# PCB_Design.net
KiCad netlist of a schematic drawn in EAGLE
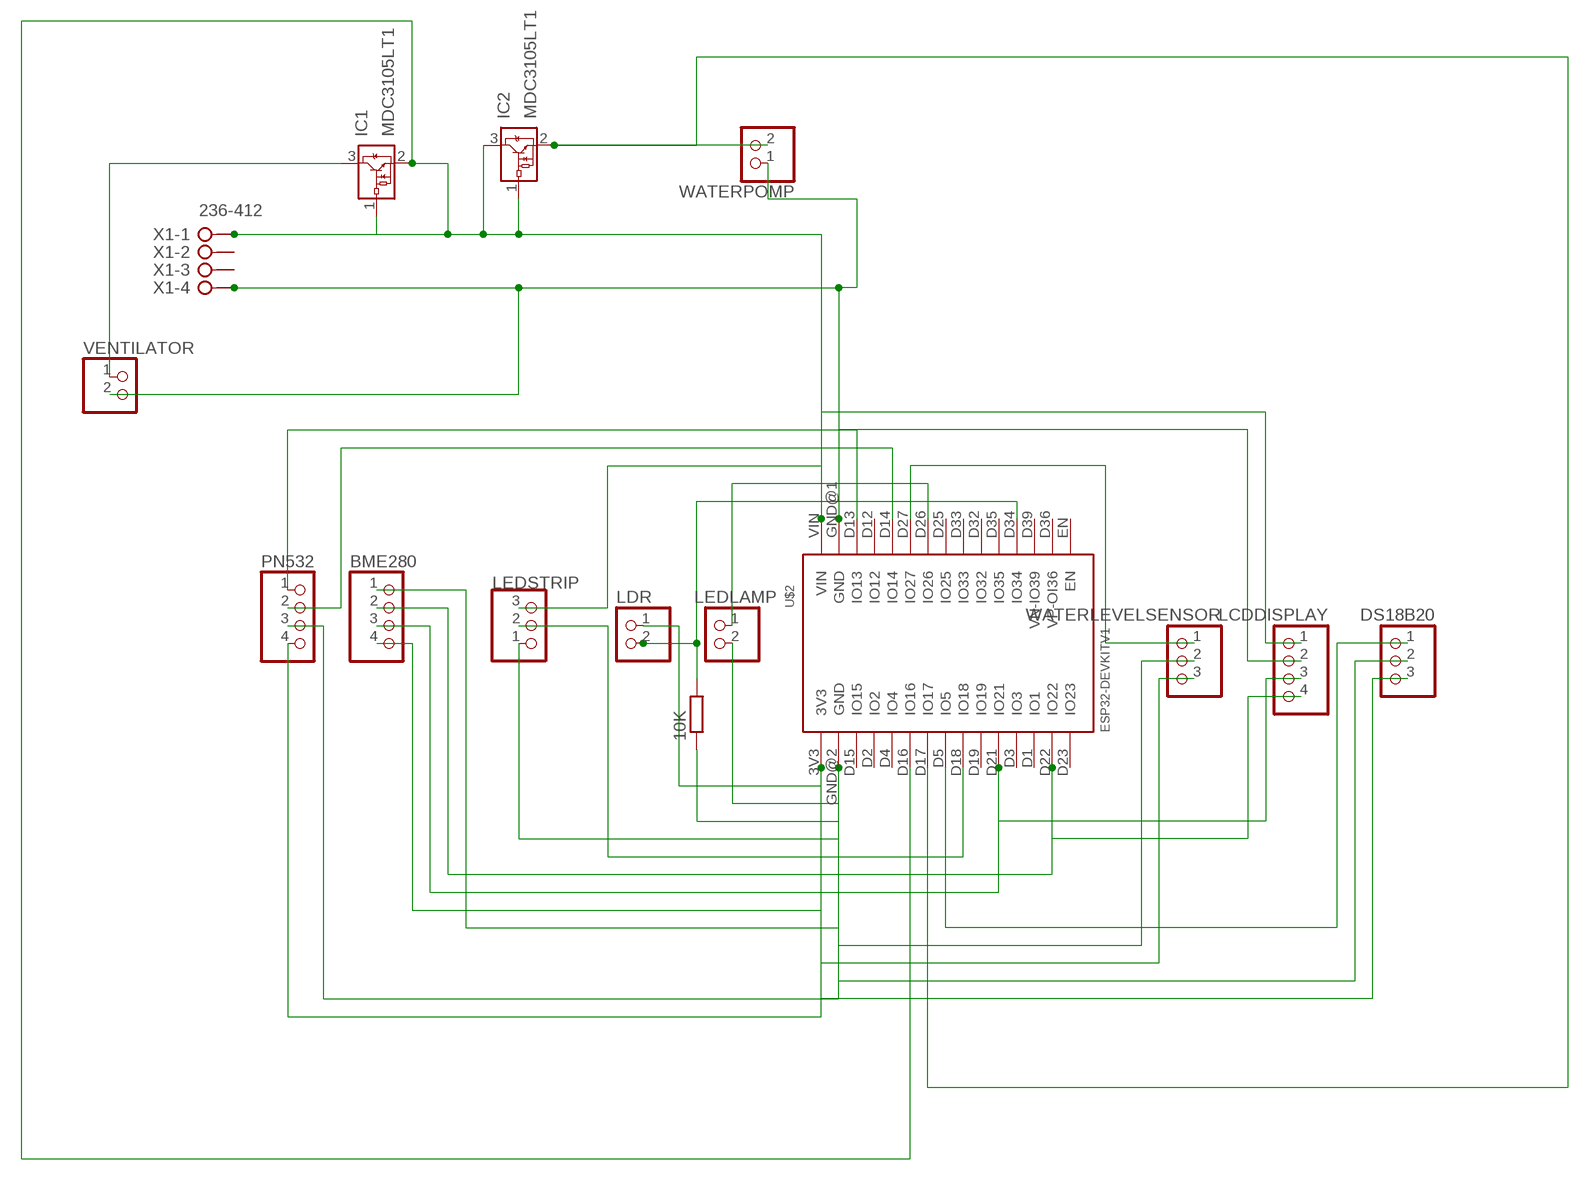
[diagram p0: schematic, sheet 1]

(export (version "E")
  (design (tool "Eeschema 10.0.6"))
  (components
    (comp (ref "10K")
      (value "R-EU_0204/7")
      (footprint "eagle-import:0204_7")
      (libsource (lib "eagle-import") (part "R-EU_0204/7"))
    )
    (comp (ref "BME280")
      (value "PINHD-1X4")
      (footprint "eagle-import:1X04")
      (libsource (lib "eagle-import") (part "PINHD-1X4"))
    )
    (comp (ref "DS18B20")
      (value "PINHD-1X3")
      (footprint "eagle-import:1X03")
      (libsource (lib "eagle-import") (part "PINHD-1X3"))
    )
    (comp (ref "IC1")
      (value "MDC3105LT1")
      (footprint "eagle-import:SOT23")
      (fields (field (name "MF") "ON SEMICONDUCTOR"))
      (libsource (lib "eagle-import") (part "MDC3105LT1"))
    )
    (comp (ref "IC2")
      (value "MDC3105LT1")
      (footprint "eagle-import:SOT23")
      (fields (field (name "MF") "ON SEMICONDUCTOR"))
      (libsource (lib "eagle-import") (part "MDC3105LT1"))
    )
    (comp (ref "LCDDISPLAY")
      (value "PINHD-1X4")
      (footprint "eagle-import:1X04")
      (libsource (lib "eagle-import") (part "PINHD-1X4"))
    )
    (comp (ref "LDR")
      (value "PINHD-1X2")
      (footprint "eagle-import:1X02")
      (libsource (lib "eagle-import") (part "PINHD-1X2"))
    )
    (comp (ref "LEDLAMP")
      (value "PINHD-1X2")
      (footprint "eagle-import:1X02")
      (libsource (lib "eagle-import") (part "PINHD-1X2"))
    )
    (comp (ref "LEDSTRIP")
      (value "PINHD-1X3")
      (footprint "eagle-import:1X03")
      (libsource (lib "eagle-import") (part "PINHD-1X3"))
    )
    (comp (ref "PN532")
      (value "PINHD-1X4")
      (footprint "eagle-import:1X04")
      (libsource (lib "eagle-import") (part "PINHD-1X4"))
    )
    (comp (ref "U$2")
      (value "ESP32DEVKITV1")
      (footprint "eagle-import:ESP32-DEVKITV1")
      (libsource (lib "eagle-import") (part "ESP32DEVKITV1"))
    )
    (comp (ref "VENTILATOR")
      (value "PINHD-1X2")
      (footprint "eagle-import:1X02")
      (libsource (lib "eagle-import") (part "PINHD-1X2"))
    )
    (comp (ref "WATERLEVELSENSOR")
      (value "PINHD-1X3")
      (footprint "eagle-import:1X03")
      (libsource (lib "eagle-import") (part "PINHD-1X3"))
    )
    (comp (ref "WATERPOMP")
      (value "PINHD-1X2")
      (footprint "eagle-import:1X02")
      (libsource (lib "eagle-import") (part "PINHD-1X2"))
    )
    (comp (ref "X1")
      (value "236-412")
      (footprint "eagle-import:236-412")
      (fields (field (name "MF") "Wago Corporation") (field (name "MPN") "0236-0412"))
      (libsource (lib "eagle-import") (part "236-412"))
    )
  )
  (nets
    (net (code "1") (name "Net-(10K-Pad1)") (class "Default")
      (node (ref "10K") (pin "1") (pinfunction "1_1") (pintype "passive"))
      (node (ref "BME280") (pin "1") (pinfunction "1_1") (pintype "passive"))
      (node (ref "DS18B20") (pin "2") (pinfunction "2_2") (pintype "passive"))
      (node (ref "LEDLAMP") (pin "2") (pinfunction "2_2") (pintype "passive"))
      (node (ref "LEDSTRIP") (pin "1") (pinfunction "1_1") (pintype "passive"))
      (node (ref "PN532") (pin "3") (pinfunction "3_3") (pintype "passive"))
      (node (ref "U$2") (pin "GND@2") (pinfunction "GND_GND@2") (pintype "bidirectional"))
      (node (ref "WATERLEVELSENSOR") (pin "2") (pinfunction "2_2") (pintype "passive"))
    )
    (net (code "2") (name "Net-(BME280-Pad4)") (class "Default")
      (node (ref "BME280") (pin "4") (pinfunction "4_4") (pintype "passive"))
      (node (ref "DS18B20") (pin "3") (pinfunction "3_3") (pintype "passive"))
      (node (ref "LDR") (pin "1") (pinfunction "1_1") (pintype "passive"))
      (node (ref "PN532") (pin "4") (pinfunction "4_4") (pintype "passive"))
      (node (ref "U$2") (pin "3V3") (pinfunction "3V3_3V3") (pintype "bidirectional"))
      (node (ref "WATERLEVELSENSOR") (pin "3") (pinfunction "3_3") (pintype "passive"))
    )
    (net (code "3") (name "Net-(IC1-GND)") (class "Default")
      (node (ref "IC1") (pin "1") (pinfunction "VIN_1") (pintype "passive"))
      (node (ref "IC1") (pin "2") (pinfunction "GND_2") (pintype "passive"))
      (node (ref "IC2") (pin "1") (pinfunction "VIN_1") (pintype "passive"))
      (node (ref "IC2") (pin "3") (pinfunction "VOUT_3") (pintype "passive"))
      (node (ref "LCDDISPLAY") (pin "1") (pinfunction "1_1") (pintype "passive"))
      (node (ref "LEDSTRIP") (pin "3") (pinfunction "3_3") (pintype "passive"))
      (node (ref "U$2") (pin "D16") (pinfunction "IO16_D16") (pintype "bidirectional"))
      (node (ref "U$2") (pin "VIN") (pinfunction "VIN_VIN") (pintype "bidirectional"))
      (node (ref "X1") (pin "1@1") (pinfunction "KL1_1@1") (pintype "passive"))
    )
    (net (code "4") (name "Net-(IC1-VOUT)") (class "Default")
      (node (ref "IC1") (pin "3") (pinfunction "VOUT_3") (pintype "passive"))
      (node (ref "VENTILATOR") (pin "1") (pinfunction "1_1") (pintype "passive"))
    )
    (net (code "5") (name "Net-(IC2-GND)") (class "Default")
      (node (ref "IC2") (pin "2") (pinfunction "GND_2") (pintype "passive"))
      (node (ref "U$2") (pin "D17") (pinfunction "IO17_D17") (pintype "bidirectional"))
      (node (ref "WATERPOMP") (pin "2") (pinfunction "2_2") (pintype "passive"))
    )
    (net (code "6") (name "Net-(U$2-IO5)") (class "Default")
      (node (ref "DS18B20") (pin "1") (pinfunction "1_1") (pintype "passive"))
      (node (ref "U$2") (pin "D5") (pinfunction "IO5_D5") (pintype "bidirectional"))
    )
    (net (code "7") (name "Net-(U$2-IO13)") (class "Default")
      (node (ref "PN532") (pin "1") (pinfunction "1_1") (pintype "passive"))
      (node (ref "U$2") (pin "D13") (pinfunction "IO13_D13") (pintype "bidirectional"))
    )
    (net (code "8") (name "Net-(U$2-IO14)") (class "Default")
      (node (ref "PN532") (pin "2") (pinfunction "2_2") (pintype "passive"))
      (node (ref "U$2") (pin "D14") (pinfunction "IO14_D14") (pintype "bidirectional"))
    )
    (net (code "9") (name "Net-(U$2-IO18)") (class "Default")
      (node (ref "LEDSTRIP") (pin "2") (pinfunction "2_2") (pintype "passive"))
      (node (ref "U$2") (pin "D18") (pinfunction "IO18_D18") (pintype "bidirectional"))
    )
    (net (code "10") (name "Net-(U$2-IO21)") (class "Default")
      (node (ref "BME280") (pin "3") (pinfunction "3_3") (pintype "passive"))
      (node (ref "LCDDISPLAY") (pin "3") (pinfunction "3_3") (pintype "passive"))
      (node (ref "U$2") (pin "D21") (pinfunction "IO21_D21") (pintype "bidirectional"))
    )
    (net (code "11") (name "Net-(U$2-IO22)") (class "Default")
      (node (ref "BME280") (pin "2") (pinfunction "2_2") (pintype "passive"))
      (node (ref "LCDDISPLAY") (pin "4") (pinfunction "4_4") (pintype "passive"))
      (node (ref "U$2") (pin "D22") (pinfunction "IO22_D22") (pintype "bidirectional"))
    )
    (net (code "12") (name "Net-(U$2-IO26)") (class "Default")
      (node (ref "LEDLAMP") (pin "1") (pinfunction "1_1") (pintype "passive"))
      (node (ref "U$2") (pin "D26") (pinfunction "IO26_D26") (pintype "bidirectional"))
    )
    (net (code "13") (name "Net-(U$2-IO27)") (class "Default")
      (node (ref "U$2") (pin "D27") (pinfunction "IO27_D27") (pintype "bidirectional"))
      (node (ref "WATERLEVELSENSOR") (pin "1") (pinfunction "1_1") (pintype "passive"))
    )
    (net (code "14") (name "Net-(U$2-IO34)") (class "Default")
      (node (ref "10K") (pin "2") (pinfunction "2_2") (pintype "passive"))
      (node (ref "LDR") (pin "2") (pinfunction "2_2") (pintype "passive"))
      (node (ref "U$2") (pin "D34") (pinfunction "IO34_D34") (pintype "bidirectional"))
    )
    (net (code "15") (name "Net-(X1G-KL1)") (class "Default")
      (node (ref "LCDDISPLAY") (pin "2") (pinfunction "2_2") (pintype "passive"))
      (node (ref "U$2") (pin "GND@1") (pinfunction "GND_GND@1") (pintype "bidirectional"))
      (node (ref "VENTILATOR") (pin "2") (pinfunction "2_2") (pintype "passive"))
      (node (ref "WATERPOMP") (pin "1") (pinfunction "1_1") (pintype "passive"))
      (node (ref "X1") (pin "4@1") (pinfunction "KL1_4@1") (pintype "passive"))
    )
    (net (code "16") (name "unconnected-(U$2-IO1-PadD1)") (class "Default")
      (node (ref "U$2") (pin "D1") (pinfunction "IO1_D1") (pintype "bidirectional"))
    )
    (net (code "17") (name "unconnected-(U$2-IO2-PadD2)") (class "Default")
      (node (ref "U$2") (pin "D2") (pinfunction "IO2_D2") (pintype "bidirectional"))
    )
    (net (code "18") (name "unconnected-(U$2-IO3-PadD3)") (class "Default")
      (node (ref "U$2") (pin "D3") (pinfunction "IO3_D3") (pintype "bidirectional"))
    )
    (net (code "19") (name "unconnected-(U$2-IO4-PadD4)") (class "Default")
      (node (ref "U$2") (pin "D4") (pinfunction "IO4_D4") (pintype "bidirectional"))
    )
    (net (code "20") (name "unconnected-(U$2-IO12-PadD12)") (class "Default")
      (node (ref "U$2") (pin "D12") (pinfunction "IO12_D12") (pintype "bidirectional"))
    )
    (net (code "21") (name "unconnected-(U$2-IO15-PadD15)") (class "Default")
      (node (ref "U$2") (pin "D15") (pinfunction "IO15_D15") (pintype "bidirectional"))
    )
    (net (code "22") (name "unconnected-(U$2-IO19-PadD19)") (class "Default")
      (node (ref "U$2") (pin "D19") (pinfunction "IO19_D19") (pintype "bidirectional"))
    )
    (net (code "23") (name "unconnected-(U$2-IO23-PadD23)") (class "Default")
      (node (ref "U$2") (pin "D23") (pinfunction "IO23_D23") (pintype "bidirectional"))
    )
    (net (code "24") (name "unconnected-(U$2-IO25-PadD25)") (class "Default")
      (node (ref "U$2") (pin "D25") (pinfunction "IO25_D25") (pintype "bidirectional"))
    )
    (net (code "25") (name "unconnected-(U$2-IO32-PadD32)") (class "Default")
      (node (ref "U$2") (pin "D32") (pinfunction "IO32_D32") (pintype "bidirectional"))
    )
    (net (code "26") (name "unconnected-(U$2-IO33-PadD33)") (class "Default")
      (node (ref "U$2") (pin "D33") (pinfunction "IO33_D33") (pintype "bidirectional"))
    )
    (net (code "27") (name "unconnected-(U$2-IO35-PadD35)") (class "Default")
      (node (ref "U$2") (pin "D35") (pinfunction "IO35_D35") (pintype "bidirectional"))
    )
    (net (code "28") (name "unconnected-(U$2-PadEN)") (class "Default")
      (node (ref "U$2") (pin "EN") (pinfunction "EN_EN") (pintype "bidirectional"))
    )
    (net (code "29") (name "unconnected-(U$2-VN-IO39-PadD39)") (class "Default")
      (node (ref "U$2") (pin "D39") (pinfunction "VN-IO39_D39") (pintype "bidirectional"))
    )
    (net (code "30") (name "unconnected-(U$2-VP-OI36-PadD36)") (class "Default")
      (node (ref "U$2") (pin "D36") (pinfunction "VP-OI36_D36") (pintype "bidirectional"))
    )
    (net (code "31") (name "unconnected-(X1A-KL2-Pad1@2)") (class "Default")
      (node (ref "X1") (pin "1@2") (pinfunction "KL2_1@2") (pintype "passive"))
    )
    (net (code "32") (name "unconnected-(X1E-KL1-Pad2@1)") (class "Default")
      (node (ref "X1") (pin "2@1") (pinfunction "KL1_2@1") (pintype "passive"))
    )
    (net (code "33") (name "unconnected-(X1E-KL2-Pad2@2)") (class "Default")
      (node (ref "X1") (pin "2@2") (pinfunction "KL2_2@2") (pintype "passive"))
    )
    (net (code "34") (name "unconnected-(X1F-KL1-Pad3@1)") (class "Default")
      (node (ref "X1") (pin "3@1") (pinfunction "KL1_3@1") (pintype "passive"))
    )
    (net (code "35") (name "unconnected-(X1F-KL2-Pad3@2)") (class "Default")
      (node (ref "X1") (pin "3@2") (pinfunction "KL2_3@2") (pintype "passive"))
    )
    (net (code "36") (name "unconnected-(X1G-KL2-Pad4@2)") (class "Default")
      (node (ref "X1") (pin "4@2") (pinfunction "KL2_4@2") (pintype "passive"))
    )
  )
)
